# PTC_Thermistor_1K_VDiv_wBuffer.net
KiCad netlist of a schematic drawn in Altium Designer
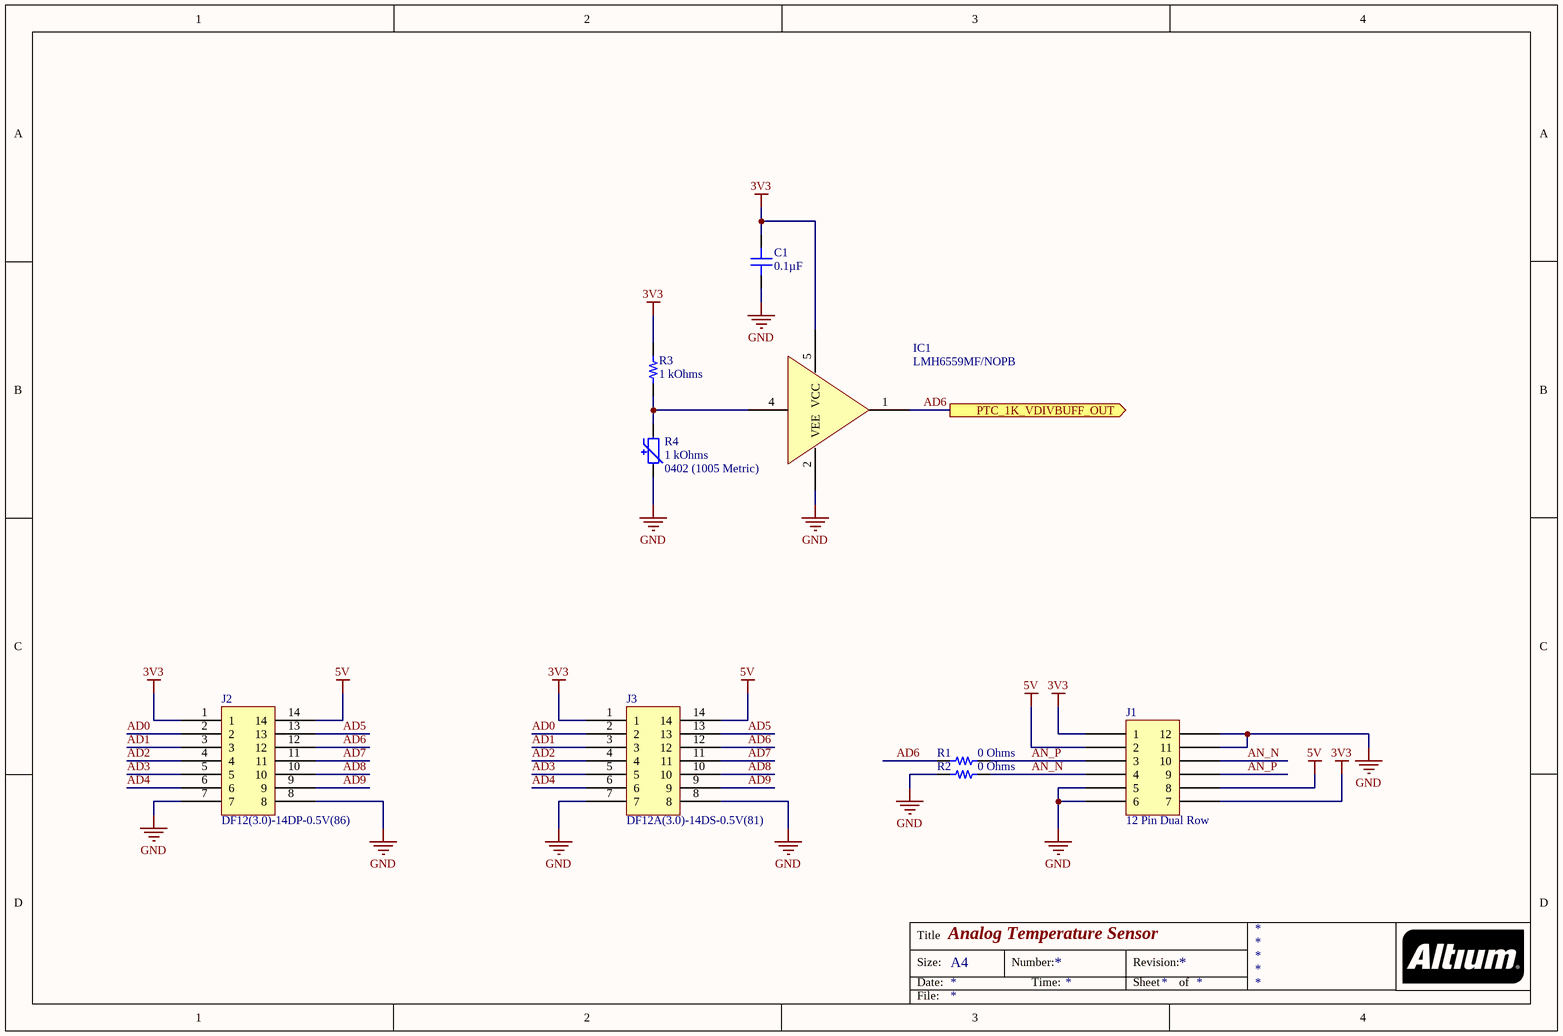
[diagram p0: PTC Thermistor 1K VDiv wBuffer.SchDoc]

(export (version "E")
  (design (tool "Eeschema 10.0.6"))
  (components
    (comp (ref "C1")
      (value "0.1µF")
      (footprint "CAP 0603_1608")
      (description "CAP CER 0.1UF 16V Y5V 0603")
      (fields (field (name "PART NUMBER") "CC0603ZRY5V7BB104") (field (name "MANUFACTURER") "Yageo"))
      (libsource (lib "altiumlibrary.com") (part "Capacitor"))
    )
    (comp (ref "IC1")
      (value "LMH6559MF/NOPB")
      (footprint "TI SOT-23-5 DBV")
      (description "IC BUFFER 1 CIRCUIT SOT23-5")
      (fields (field (name "MANUFACTURER") "Texas Instruments"))
      (libsource (lib "altiumlibrary.com") (part "TI LMH6559"))
    )
    (comp (ref "J1")
      (value "12 Pin Dual Row")
      (footprint "TE 5650118-3 Card Edge")
      (libsource (lib "CelestialUseful") (part "12 Pin Dual Row"))
    )
    (comp (ref "J2")
      (value "DF12(3.0)-14DP-0.5V(86)")
      (footprint "HIROSE DF12 3.0-14DP-0.5V 86")
      (description "CONN HDR 14POS SMD GOLD")
      (fields (field (name "MANUFACTURER") "Hirose Electric Co Ltd"))
      (libsource (lib "altiumlibrary.com") (part "14 Pin Dual Row"))
    )
    (comp (ref "J3")
      (value "DF12A(3.0)-14DS-0.5V(81)")
      (footprint "HIROSE DF12A 3.0-14DS-0.5V 81")
      (description "CONN RCPT 14POS SMD GOLD")
      (fields (field (name "MANUFACTURER") "Hirose Electric Co Ltd"))
      (libsource (lib "altiumlibrary.com") (part "14 Pin Dual Row"))
    )
    (comp (ref "R1")
      (value "0 Ohms")
      (footprint "RES 0603_1608")
      (description "RES SMD 0 OHM JUMPER 1/10W 0603")
      (fields
        (field (name "PART NUMBER") "ERJ-3GEY0R00V")
        (field (name "MANUFACTURER") "Panasonic Electronic Components")
      )
      (libsource (lib "altiumlibrary.com") (part "Resistor"))
    )
    (comp (ref "R2")
      (value "0 Ohms")
      (footprint "RES 0603_1608")
      (description "RES SMD 0 OHM JUMPER 1/10W 0603")
      (fields
        (field (name "PART NUMBER") "ERJ-3GEY0R00V")
        (field (name "MANUFACTURER") "Panasonic Electronic Components")
      )
      (libsource (lib "altiumlibrary.com") (part "Resistor"))
    )
    (comp (ref "R3")
      (value "1 kOhms")
      (footprint "RES 0603_1608")
      (description "RES SMD 1K OHM 1% 1/10W 0603")
      (fields
        (field (name "PART NUMBER") "ERJ-3EKF1001V")
        (field (name "MANUFACTURER") "Panasonic Electronic Components")
      )
      (libsource (lib "altiumlibrary.com") (part "Resistor"))
    )
    (comp (ref "R4")
      (value "1 kOhms")
      (footprint "PTC 0402_1005")
      (description "THERMISTOR PTC 1K OHM 5% 0402")
      (fields
        (field (name "PART NUMBER") "PRF15AR102RB6RC")
        (field (name "MANUFACTURER") "Murata Electronics")
        (field (name "PACKAGE / CASE") "0402 (1005 Metric)")
      )
      (libsource (lib "altiumlibrary.com") (part "Thermistor PTC"))
    )
  )
  (nets
    (net (code "1") (name "/AD0") (class "Default")
      (node (ref "J2") (pin "2") (pinfunction "2_2") (pintype "passive"))
      (node (ref "J3") (pin "2") (pinfunction "2_2") (pintype "passive"))
    )
    (net (code "2") (name "/AD1") (class "Default")
      (node (ref "J2") (pin "3") (pinfunction "3_3") (pintype "passive"))
      (node (ref "J3") (pin "3") (pinfunction "3_3") (pintype "passive"))
    )
    (net (code "3") (name "/AD2") (class "Default")
      (node (ref "J2") (pin "4") (pinfunction "4_4") (pintype "passive"))
      (node (ref "J3") (pin "4") (pinfunction "4_4") (pintype "passive"))
    )
    (net (code "4") (name "/AD3") (class "Default")
      (node (ref "J2") (pin "5") (pinfunction "5_5") (pintype "passive"))
      (node (ref "J3") (pin "5") (pinfunction "5_5") (pintype "passive"))
    )
    (net (code "5") (name "/AD4") (class "Default")
      (node (ref "J2") (pin "6") (pinfunction "6_6") (pintype "passive"))
      (node (ref "J3") (pin "6") (pinfunction "6_6") (pintype "passive"))
    )
    (net (code "6") (name "/AD5") (class "Default")
      (node (ref "J2") (pin "13") (pinfunction "13_13") (pintype "passive"))
      (node (ref "J3") (pin "13") (pinfunction "13_13") (pintype "passive"))
    )
    (net (code "7") (name "/AD6") (class "Default")
      (node (ref "IC1") (pin "1") (pinfunction "OUT_1") (pintype "passive"))
      (node (ref "J2") (pin "12") (pinfunction "12_12") (pintype "passive"))
      (node (ref "J3") (pin "12") (pinfunction "12_12") (pintype "passive"))
      (node (ref "R1") (pin "1") (pinfunction "1_1") (pintype "passive"))
    )
    (net (code "8") (name "/AD7") (class "Default")
      (node (ref "J2") (pin "11") (pinfunction "11_11") (pintype "passive"))
      (node (ref "J3") (pin "11") (pinfunction "11_11") (pintype "passive"))
    )
    (net (code "9") (name "/AD8") (class "Default")
      (node (ref "J2") (pin "10") (pinfunction "10_10") (pintype "passive"))
      (node (ref "J3") (pin "10") (pinfunction "10_10") (pintype "passive"))
    )
    (net (code "10") (name "/AD9") (class "Default")
      (node (ref "J2") (pin "9") (pinfunction "9_9") (pintype "passive"))
      (node (ref "J3") (pin "9") (pinfunction "9_9") (pintype "passive"))
    )
    (net (code "11") (name "/AN_N") (class "Default")
      (node (ref "J1") (pin "10") (pinfunction "10_10") (pintype "passive"))
      (node (ref "J1") (pin "4") (pinfunction "4_4") (pintype "passive"))
      (node (ref "R2") (pin "2") (pinfunction "2_2") (pintype "passive"))
    )
    (net (code "12") (name "/AN_P") (class "Default")
      (node (ref "J1") (pin "3") (pinfunction "3_3") (pintype "passive"))
      (node (ref "J1") (pin "9") (pinfunction "9_9") (pintype "passive"))
      (node (ref "R1") (pin "2") (pinfunction "2_2") (pintype "passive"))
    )
    (net (code "13") (name "3V3") (class "Default")
      (node (ref "C1") (pin "2") (pinfunction "2_2") (pintype "passive"))
      (node (ref "IC1") (pin "5") (pinfunction "VCC_5") (pintype "power_in"))
      (node (ref "J1") (pin "1") (pinfunction "1_1") (pintype "passive"))
      (node (ref "J1") (pin "7") (pinfunction "7_7") (pintype "passive"))
      (node (ref "J2") (pin "1") (pinfunction "1_1") (pintype "passive"))
      (node (ref "J3") (pin "1") (pinfunction "1_1") (pintype "passive"))
      (node (ref "R3") (pin "2") (pinfunction "2_2") (pintype "passive"))
    )
    (net (code "14") (name "5V") (class "Default")
      (node (ref "J1") (pin "2") (pinfunction "2_2") (pintype "passive"))
      (node (ref "J1") (pin "8") (pinfunction "8_8") (pintype "passive"))
      (node (ref "J2") (pin "14") (pinfunction "14_14") (pintype "passive"))
      (node (ref "J3") (pin "14") (pinfunction "14_14") (pintype "passive"))
    )
    (net (code "15") (name "GND") (class "Default")
      (node (ref "C1") (pin "1") (pinfunction "1_1") (pintype "passive"))
      (node (ref "IC1") (pin "2") (pinfunction "VEE_2") (pintype "power_in"))
      (node (ref "J1") (pin "11") (pinfunction "11_11") (pintype "passive"))
      (node (ref "J1") (pin "12") (pinfunction "12_12") (pintype "passive"))
      (node (ref "J1") (pin "5") (pinfunction "5_5") (pintype "passive"))
      (node (ref "J1") (pin "6") (pinfunction "6_6") (pintype "passive"))
      (node (ref "J2") (pin "7") (pinfunction "7_7") (pintype "passive"))
      (node (ref "J2") (pin "8") (pinfunction "8_8") (pintype "passive"))
      (node (ref "J3") (pin "7") (pinfunction "7_7") (pintype "passive"))
      (node (ref "J3") (pin "8") (pinfunction "8_8") (pintype "passive"))
      (node (ref "R2") (pin "1") (pinfunction "1_1") (pintype "passive"))
      (node (ref "R4") (pin "2") (pinfunction "2_2") (pintype "passive"))
    )
    (net (code "16") (name "Net-(IC1-IN)") (class "Default")
      (node (ref "IC1") (pin "4") (pinfunction "IN_4") (pintype "passive"))
      (node (ref "R3") (pin "1") (pinfunction "1_1") (pintype "passive"))
      (node (ref "R4") (pin "1") (pinfunction "1_1") (pintype "passive"))
    )
  )
)
